# Arduino_Mega_Extended_Breakout_Shield.net
KiCad netlist of a schematic drawn in EAGLE
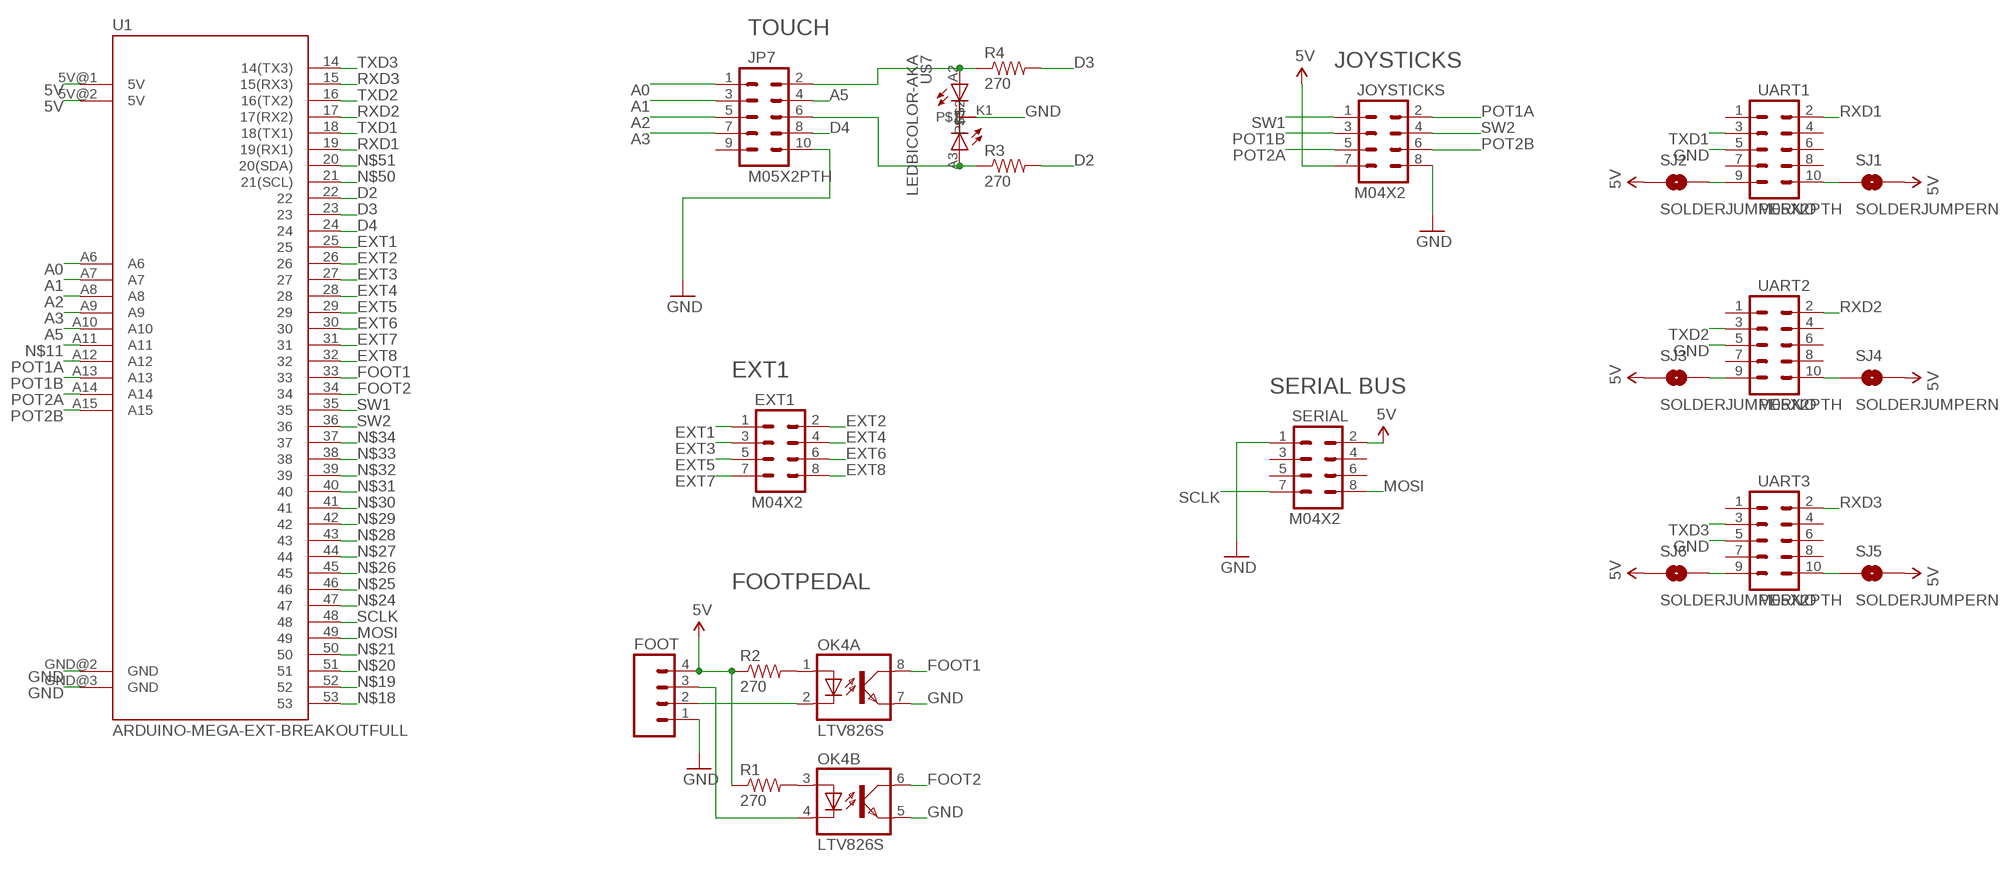
[diagram p0: schematic, sheet 1]

(export (version "E")
  (design (tool "Eeschema 10.0.6"))
  (components
    (comp (ref "EXT1")
      (value "M04X2")
      (footprint "eagle-import:2X4")
      (libsource (lib "eagle-import") (part "M04X2"))
    )
    (comp (ref "FOOT")
      (value "M04LOCK")
      (footprint "eagle-import:1X04_LOCK")
      (libsource (lib "eagle-import") (part "M04LOCK"))
    )
    (comp (ref "JOYSTICKS")
      (value "M04X2")
      (footprint "eagle-import:2X4")
      (libsource (lib "eagle-import") (part "M04X2"))
    )
    (comp (ref "JP7")
      (value "M05X2PTH")
      (footprint "eagle-import:AVR_ICSP")
      (libsource (lib "eagle-import") (part "M05X2PTH"))
    )
    (comp (ref "OK4")
      (value "LTV826S")
      (footprint "eagle-import:DIL8-SMD")
      (libsource (lib "eagle-import") (part "LTV826S"))
    )
    (comp (ref "R1")
      (value "270")
      (footprint "eagle-import:0603-RES")
      (libsource (lib "eagle-import") (part "RESISTOR0603-RES"))
    )
    (comp (ref "R2")
      (value "270")
      (footprint "eagle-import:0603-RES")
      (libsource (lib "eagle-import") (part "RESISTOR0603-RES"))
    )
    (comp (ref "R3")
      (value "270")
      (footprint "eagle-import:0603-RES")
      (libsource (lib "eagle-import") (part "RESISTOR0603-RES"))
    )
    (comp (ref "R4")
      (value "270")
      (footprint "eagle-import:0603-RES")
      (libsource (lib "eagle-import") (part "RESISTOR0603-RES"))
    )
    (comp (ref "SERIAL")
      (value "M04X2")
      (footprint "eagle-import:2X4")
      (libsource (lib "eagle-import") (part "M04X2"))
    )
    (comp (ref "SJ1")
      (value "SOLDERJUMPERNO")
      (footprint "eagle-import:SJ_2S-NO")
      (libsource (lib "eagle-import") (part "SOLDERJUMPERNO"))
    )
    (comp (ref "SJ2")
      (value "SOLDERJUMPERNO")
      (footprint "eagle-import:SJ_2S-NO")
      (libsource (lib "eagle-import") (part "SOLDERJUMPERNO"))
    )
    (comp (ref "SJ3")
      (value "SOLDERJUMPERNO")
      (footprint "eagle-import:SJ_2S-NO")
      (libsource (lib "eagle-import") (part "SOLDERJUMPERNO"))
    )
    (comp (ref "SJ4")
      (value "SOLDERJUMPERNO")
      (footprint "eagle-import:SJ_2S-NO")
      (libsource (lib "eagle-import") (part "SOLDERJUMPERNO"))
    )
    (comp (ref "SJ5")
      (value "SOLDERJUMPERNO")
      (footprint "eagle-import:SJ_2S-NO")
      (libsource (lib "eagle-import") (part "SOLDERJUMPERNO"))
    )
    (comp (ref "SJ6")
      (value "SOLDERJUMPERNO")
      (footprint "eagle-import:SJ_2S-NO")
      (libsource (lib "eagle-import") (part "SOLDERJUMPERNO"))
    )
    (comp (ref "U$7")
      (value "LEDBICOLOR-AKA")
      (footprint "eagle-import:LED5MM-BICOLOR")
      (libsource (lib "eagle-import") (part "LEDBICOLOR-AKA"))
    )
    (comp (ref "U1")
      (value "ARDUINO-MEGA-EXT-BREAKOUTFULL")
      (footprint "eagle-import:ARDUINO_MEGA_EXT_BREAKOUT")
      (libsource (lib "eagle-import") (part "ARDUINO-MEGA-EXT-BREAKOUTFULL"))
    )
    (comp (ref "UART1")
      (value "M05X2PTH")
      (footprint "eagle-import:AVR_ICSP")
      (libsource (lib "eagle-import") (part "M05X2PTH"))
    )
    (comp (ref "UART2")
      (value "M05X2PTH")
      (footprint "eagle-import:AVR_ICSP")
      (libsource (lib "eagle-import") (part "M05X2PTH"))
    )
    (comp (ref "UART3")
      (value "M05X2PTH")
      (footprint "eagle-import:AVR_ICSP")
      (libsource (lib "eagle-import") (part "M05X2PTH"))
    )
  )
  (nets
    (net (code "1") (name "/A0") (class "Default")
      (node (ref "JP7") (pin "1") (pinfunction "1_1") (pintype "passive"))
      (node (ref "U1") (pin "A6") (pinfunction "A6_A6") (pintype "bidirectional"))
    )
    (net (code "2") (name "/A1") (class "Default")
      (node (ref "JP7") (pin "3") (pinfunction "3_3") (pintype "passive"))
      (node (ref "U1") (pin "A7") (pinfunction "A7_A7") (pintype "bidirectional"))
    )
    (net (code "3") (name "/A2") (class "Default")
      (node (ref "JP7") (pin "5") (pinfunction "5_5") (pintype "passive"))
      (node (ref "U1") (pin "A8") (pinfunction "A8_A8") (pintype "bidirectional"))
    )
    (net (code "4") (name "/A3") (class "Default")
      (node (ref "JP7") (pin "7") (pinfunction "7_7") (pintype "passive"))
      (node (ref "U1") (pin "A9") (pinfunction "A9_A9") (pintype "bidirectional"))
    )
    (net (code "5") (name "/A5") (class "Default")
      (node (ref "JP7") (pin "4") (pinfunction "4_4") (pintype "passive"))
      (node (ref "U1") (pin "A10") (pinfunction "A10_A10") (pintype "bidirectional"))
    )
    (net (code "6") (name "/D2") (class "Default")
      (node (ref "R3") (pin "2") (pinfunction "2_2") (pintype "passive"))
      (node (ref "U1") (pin "22") (pinfunction "22_22") (pintype "bidirectional"))
    )
    (net (code "7") (name "/D3") (class "Default")
      (node (ref "R4") (pin "2") (pinfunction "2_2") (pintype "passive"))
      (node (ref "U1") (pin "23") (pinfunction "23_23") (pintype "bidirectional"))
    )
    (net (code "8") (name "/D4") (class "Default")
      (node (ref "JP7") (pin "8") (pinfunction "8_8") (pintype "passive"))
      (node (ref "U1") (pin "24") (pinfunction "24_24") (pintype "bidirectional"))
    )
    (net (code "9") (name "/EXT1") (class "Default")
      (node (ref "EXT1") (pin "1") (pinfunction "1_1") (pintype "passive"))
      (node (ref "U1") (pin "25") (pinfunction "25_25") (pintype "bidirectional"))
    )
    (net (code "10") (name "/EXT2") (class "Default")
      (node (ref "EXT1") (pin "2") (pinfunction "2_2") (pintype "passive"))
      (node (ref "U1") (pin "26") (pinfunction "26_26") (pintype "bidirectional"))
    )
    (net (code "11") (name "/EXT3") (class "Default")
      (node (ref "EXT1") (pin "3") (pinfunction "3_3") (pintype "passive"))
      (node (ref "U1") (pin "27") (pinfunction "27_27") (pintype "bidirectional"))
    )
    (net (code "12") (name "/EXT4") (class "Default")
      (node (ref "EXT1") (pin "4") (pinfunction "4_4") (pintype "passive"))
      (node (ref "U1") (pin "28") (pinfunction "28_28") (pintype "bidirectional"))
    )
    (net (code "13") (name "/EXT5") (class "Default")
      (node (ref "EXT1") (pin "5") (pinfunction "5_5") (pintype "passive"))
      (node (ref "U1") (pin "29") (pinfunction "29_29") (pintype "bidirectional"))
    )
    (net (code "14") (name "/EXT6") (class "Default")
      (node (ref "EXT1") (pin "6") (pinfunction "6_6") (pintype "passive"))
      (node (ref "U1") (pin "30") (pinfunction "30_30") (pintype "bidirectional"))
    )
    (net (code "15") (name "/EXT7") (class "Default")
      (node (ref "EXT1") (pin "7") (pinfunction "7_7") (pintype "passive"))
      (node (ref "U1") (pin "31") (pinfunction "31_31") (pintype "bidirectional"))
    )
    (net (code "16") (name "/EXT8") (class "Default")
      (node (ref "EXT1") (pin "8") (pinfunction "8_8") (pintype "passive"))
      (node (ref "U1") (pin "32") (pinfunction "32_32") (pintype "bidirectional"))
    )
    (net (code "17") (name "/FOOT1") (class "Default")
      (node (ref "OK4") (pin "8") (pinfunction "COL_8") (pintype "passive"))
      (node (ref "U1") (pin "33") (pinfunction "33_33") (pintype "bidirectional"))
    )
    (net (code "18") (name "/FOOT2") (class "Default")
      (node (ref "OK4") (pin "6") (pinfunction "COL_6") (pintype "passive"))
      (node (ref "U1") (pin "34") (pinfunction "34_34") (pintype "bidirectional"))
    )
    (net (code "19") (name "/MOSI") (class "Default")
      (node (ref "SERIAL") (pin "8") (pinfunction "8_8") (pintype "passive"))
      (node (ref "U1") (pin "49") (pinfunction "49_49") (pintype "bidirectional"))
    )
    (net (code "20") (name "/N$11") (class "Default")
      (node (ref "U1") (pin "A11") (pinfunction "A11_A11") (pintype "bidirectional"))
    )
    (net (code "21") (name "/N$18") (class "Default")
      (node (ref "U1") (pin "53") (pinfunction "53_53") (pintype "bidirectional"))
    )
    (net (code "22") (name "/N$19") (class "Default")
      (node (ref "U1") (pin "52") (pinfunction "52_52") (pintype "bidirectional"))
    )
    (net (code "23") (name "/N$20") (class "Default")
      (node (ref "U1") (pin "51") (pinfunction "51_51") (pintype "bidirectional"))
    )
    (net (code "24") (name "/N$21") (class "Default")
      (node (ref "U1") (pin "50") (pinfunction "50_50") (pintype "bidirectional"))
    )
    (net (code "25") (name "/N$24") (class "Default")
      (node (ref "U1") (pin "47") (pinfunction "47_47") (pintype "bidirectional"))
    )
    (net (code "26") (name "/N$25") (class "Default")
      (node (ref "U1") (pin "46") (pinfunction "46_46") (pintype "bidirectional"))
    )
    (net (code "27") (name "/N$26") (class "Default")
      (node (ref "U1") (pin "45") (pinfunction "45_45") (pintype "bidirectional"))
    )
    (net (code "28") (name "/N$27") (class "Default")
      (node (ref "U1") (pin "44") (pinfunction "44_44") (pintype "bidirectional"))
    )
    (net (code "29") (name "/N$28") (class "Default")
      (node (ref "U1") (pin "43") (pinfunction "43_43") (pintype "bidirectional"))
    )
    (net (code "30") (name "/N$29") (class "Default")
      (node (ref "U1") (pin "42") (pinfunction "42_42") (pintype "bidirectional"))
    )
    (net (code "31") (name "/N$30") (class "Default")
      (node (ref "U1") (pin "41") (pinfunction "41_41") (pintype "bidirectional"))
    )
    (net (code "32") (name "/N$31") (class "Default")
      (node (ref "U1") (pin "40") (pinfunction "40_40") (pintype "bidirectional"))
    )
    (net (code "33") (name "/N$32") (class "Default")
      (node (ref "U1") (pin "39") (pinfunction "39_39") (pintype "bidirectional"))
    )
    (net (code "34") (name "/N$33") (class "Default")
      (node (ref "U1") (pin "38") (pinfunction "38_38") (pintype "bidirectional"))
    )
    (net (code "35") (name "/N$34") (class "Default")
      (node (ref "U1") (pin "37") (pinfunction "37_37") (pintype "bidirectional"))
    )
    (net (code "36") (name "/N$50") (class "Default")
      (node (ref "U1") (pin "21") (pinfunction "21(SCL)_21") (pintype "bidirectional"))
    )
    (net (code "37") (name "/N$51") (class "Default")
      (node (ref "U1") (pin "20") (pinfunction "20(SDA)_20") (pintype "bidirectional"))
    )
    (net (code "38") (name "/POT1A") (class "Default")
      (node (ref "JOYSTICKS") (pin "2") (pinfunction "2_2") (pintype "passive"))
      (node (ref "U1") (pin "A12") (pinfunction "A12_A12") (pintype "bidirectional"))
    )
    (net (code "39") (name "/POT1B") (class "Default")
      (node (ref "JOYSTICKS") (pin "3") (pinfunction "3_3") (pintype "passive"))
      (node (ref "U1") (pin "A13") (pinfunction "A13_A13") (pintype "bidirectional"))
    )
    (net (code "40") (name "/POT2A") (class "Default")
      (node (ref "JOYSTICKS") (pin "5") (pinfunction "5_5") (pintype "passive"))
      (node (ref "U1") (pin "A14") (pinfunction "A14_A14") (pintype "bidirectional"))
    )
    (net (code "41") (name "/POT2B") (class "Default")
      (node (ref "JOYSTICKS") (pin "6") (pinfunction "6_6") (pintype "passive"))
      (node (ref "U1") (pin "A15") (pinfunction "A15_A15") (pintype "bidirectional"))
    )
    (net (code "42") (name "/RXD1") (class "Default")
      (node (ref "U1") (pin "19") (pinfunction "19(RX1)_19") (pintype "bidirectional"))
      (node (ref "UART1") (pin "2") (pinfunction "2_2") (pintype "passive"))
    )
    (net (code "43") (name "/RXD2") (class "Default")
      (node (ref "U1") (pin "17") (pinfunction "17(RX2)_17") (pintype "bidirectional"))
      (node (ref "UART2") (pin "2") (pinfunction "2_2") (pintype "passive"))
    )
    (net (code "44") (name "/RXD3") (class "Default")
      (node (ref "U1") (pin "15") (pinfunction "15(RX3)_15") (pintype "bidirectional"))
      (node (ref "UART3") (pin "2") (pinfunction "2_2") (pintype "passive"))
    )
    (net (code "45") (name "/SCLK") (class "Default")
      (node (ref "SERIAL") (pin "7") (pinfunction "7_7") (pintype "passive"))
      (node (ref "U1") (pin "48") (pinfunction "48_48") (pintype "bidirectional"))
    )
    (net (code "46") (name "/SW1") (class "Default")
      (node (ref "JOYSTICKS") (pin "1") (pinfunction "1_1") (pintype "passive"))
      (node (ref "U1") (pin "35") (pinfunction "35_35") (pintype "bidirectional"))
    )
    (net (code "47") (name "/SW2") (class "Default")
      (node (ref "JOYSTICKS") (pin "4") (pinfunction "4_4") (pintype "passive"))
      (node (ref "U1") (pin "36") (pinfunction "36_36") (pintype "bidirectional"))
    )
    (net (code "48") (name "/TXD1") (class "Default")
      (node (ref "U1") (pin "18") (pinfunction "18(TX1)_18") (pintype "bidirectional"))
      (node (ref "UART1") (pin "3") (pinfunction "3_3") (pintype "passive"))
    )
    (net (code "49") (name "/TXD2") (class "Default")
      (node (ref "U1") (pin "16") (pinfunction "16(TX2)_16") (pintype "bidirectional"))
      (node (ref "UART2") (pin "3") (pinfunction "3_3") (pintype "passive"))
    )
    (net (code "50") (name "/TXD3") (class "Default")
      (node (ref "U1") (pin "14") (pinfunction "14(TX3)_14") (pintype "bidirectional"))
      (node (ref "UART3") (pin "3") (pinfunction "3_3") (pintype "passive"))
    )
    (net (code "51") (name "5V") (class "Default")
      (node (ref "FOOT") (pin "4") (pinfunction "4_4") (pintype "passive"))
      (node (ref "JOYSTICKS") (pin "7") (pinfunction "7_7") (pintype "passive"))
      (node (ref "R1") (pin "1") (pinfunction "1_1") (pintype "passive"))
      (node (ref "R2") (pin "1") (pinfunction "1_1") (pintype "passive"))
      (node (ref "SERIAL") (pin "2") (pinfunction "2_2") (pintype "passive"))
      (node (ref "SJ1") (pin "2") (pinfunction "2_2") (pintype "passive"))
      (node (ref "SJ2") (pin "1") (pinfunction "1_1") (pintype "passive"))
      (node (ref "SJ3") (pin "1") (pinfunction "1_1") (pintype "passive"))
      (node (ref "SJ4") (pin "2") (pinfunction "2_2") (pintype "passive"))
      (node (ref "SJ5") (pin "2") (pinfunction "2_2") (pintype "passive"))
      (node (ref "SJ6") (pin "1") (pinfunction "1_1") (pintype "passive"))
      (node (ref "U1") (pin "5V@1") (pinfunction "5V_5V@1") (pintype "bidirectional"))
      (node (ref "U1") (pin "5V@2") (pinfunction "5V_5V@2") (pintype "bidirectional"))
    )
    (net (code "52") (name "GND") (class "Default")
      (node (ref "FOOT") (pin "1") (pinfunction "1_1") (pintype "passive"))
      (node (ref "JOYSTICKS") (pin "8") (pinfunction "8_8") (pintype "passive"))
      (node (ref "JP7") (pin "10") (pinfunction "10_10") (pintype "passive"))
      (node (ref "OK4") (pin "5") (pinfunction "EMIT_5") (pintype "passive"))
      (node (ref "OK4") (pin "7") (pinfunction "EMIT_7") (pintype "passive"))
      (node (ref "SERIAL") (pin "1") (pinfunction "1_1") (pintype "passive"))
      (node (ref "U$7") (pin "K1") (pinfunction "P$1_K1") (pintype "bidirectional"))
      (node (ref "U1") (pin "GND@2") (pinfunction "GND_GND@2") (pintype "bidirectional"))
      (node (ref "U1") (pin "GND@3") (pinfunction "GND_GND@3") (pintype "bidirectional"))
      (node (ref "UART1") (pin "5") (pinfunction "5_5") (pintype "passive"))
      (node (ref "UART2") (pin "5") (pinfunction "5_5") (pintype "passive"))
      (node (ref "UART3") (pin "5") (pinfunction "5_5") (pintype "passive"))
    )
    (net (code "53") (name "Net-(OK4A-A)") (class "Default")
      (node (ref "OK4") (pin "1") (pinfunction "A_1") (pintype "passive"))
      (node (ref "R2") (pin "2") (pinfunction "2_2") (pintype "passive"))
    )
    (net (code "54") (name "Net-(OK4A-C)") (class "Default")
      (node (ref "FOOT") (pin "2") (pinfunction "2_2") (pintype "passive"))
      (node (ref "OK4") (pin "2") (pinfunction "C_2") (pintype "passive"))
    )
    (net (code "55") (name "Net-(OK4B-A)") (class "Default")
      (node (ref "OK4") (pin "3") (pinfunction "A_3") (pintype "passive"))
      (node (ref "R1") (pin "2") (pinfunction "2_2") (pintype "passive"))
    )
    (net (code "56") (name "Net-(OK4B-C)") (class "Default")
      (node (ref "FOOT") (pin "3") (pinfunction "3_3") (pintype "passive"))
      (node (ref "OK4") (pin "4") (pinfunction "C_4") (pintype "passive"))
    )
    (net (code "57") (name "Net-(SJ1-Pad1)") (class "Default")
      (node (ref "SJ1") (pin "1") (pinfunction "1_1") (pintype "passive"))
      (node (ref "UART1") (pin "10") (pinfunction "10_10") (pintype "passive"))
    )
    (net (code "58") (name "Net-(SJ2-Pad2)") (class "Default")
      (node (ref "SJ2") (pin "2") (pinfunction "2_2") (pintype "passive"))
      (node (ref "UART1") (pin "9") (pinfunction "9_9") (pintype "passive"))
    )
    (net (code "59") (name "Net-(SJ3-Pad2)") (class "Default")
      (node (ref "SJ3") (pin "2") (pinfunction "2_2") (pintype "passive"))
      (node (ref "UART2") (pin "9") (pinfunction "9_9") (pintype "passive"))
    )
    (net (code "60") (name "Net-(SJ4-Pad1)") (class "Default")
      (node (ref "SJ4") (pin "1") (pinfunction "1_1") (pintype "passive"))
      (node (ref "UART2") (pin "10") (pinfunction "10_10") (pintype "passive"))
    )
    (net (code "61") (name "Net-(SJ5-Pad1)") (class "Default")
      (node (ref "SJ5") (pin "1") (pinfunction "1_1") (pintype "passive"))
      (node (ref "UART3") (pin "10") (pinfunction "10_10") (pintype "passive"))
    )
    (net (code "62") (name "Net-(SJ6-Pad2)") (class "Default")
      (node (ref "SJ6") (pin "2") (pinfunction "2_2") (pintype "passive"))
      (node (ref "UART3") (pin "9") (pinfunction "9_9") (pintype "passive"))
    )
    (net (code "63") (name "Net-(U$7-P$2)") (class "Default")
      (node (ref "JP7") (pin "2") (pinfunction "2_2") (pintype "passive"))
      (node (ref "R4") (pin "1") (pinfunction "1_1") (pintype "passive"))
      (node (ref "U$7") (pin "A2") (pinfunction "P$2_A2") (pintype "bidirectional"))
    )
    (net (code "64") (name "Net-(U$7-P$3)") (class "Default")
      (node (ref "JP7") (pin "6") (pinfunction "6_6") (pintype "passive"))
      (node (ref "R3") (pin "1") (pinfunction "1_1") (pintype "passive"))
      (node (ref "U$7") (pin "A3") (pinfunction "P$3_A3") (pintype "bidirectional"))
    )
    (net (code "65") (name "unconnected-(JP7-Pad9)") (class "Default")
      (node (ref "JP7") (pin "9") (pinfunction "9_9") (pintype "passive"))
    )
    (net (code "66") (name "unconnected-(SERIAL-Pad3)") (class "Default")
      (node (ref "SERIAL") (pin "3") (pinfunction "3_3") (pintype "passive"))
    )
    (net (code "67") (name "unconnected-(SERIAL-Pad4)") (class "Default")
      (node (ref "SERIAL") (pin "4") (pinfunction "4_4") (pintype "passive"))
    )
    (net (code "68") (name "unconnected-(SERIAL-Pad5)") (class "Default")
      (node (ref "SERIAL") (pin "5") (pinfunction "5_5") (pintype "passive"))
    )
    (net (code "69") (name "unconnected-(SERIAL-Pad6)") (class "Default")
      (node (ref "SERIAL") (pin "6") (pinfunction "6_6") (pintype "passive"))
    )
    (net (code "70") (name "unconnected-(UART1-Pad1)") (class "Default")
      (node (ref "UART1") (pin "1") (pinfunction "1_1") (pintype "passive"))
    )
    (net (code "71") (name "unconnected-(UART1-Pad4)") (class "Default")
      (node (ref "UART1") (pin "4") (pinfunction "4_4") (pintype "passive"))
    )
    (net (code "72") (name "unconnected-(UART1-Pad6)") (class "Default")
      (node (ref "UART1") (pin "6") (pinfunction "6_6") (pintype "passive"))
    )
    (net (code "73") (name "unconnected-(UART1-Pad7)") (class "Default")
      (node (ref "UART1") (pin "7") (pinfunction "7_7") (pintype "passive"))
    )
    (net (code "74") (name "unconnected-(UART1-Pad8)") (class "Default")
      (node (ref "UART1") (pin "8") (pinfunction "8_8") (pintype "passive"))
    )
    (net (code "75") (name "unconnected-(UART2-Pad1)") (class "Default")
      (node (ref "UART2") (pin "1") (pinfunction "1_1") (pintype "passive"))
    )
    (net (code "76") (name "unconnected-(UART2-Pad4)") (class "Default")
      (node (ref "UART2") (pin "4") (pinfunction "4_4") (pintype "passive"))
    )
    (net (code "77") (name "unconnected-(UART2-Pad6)") (class "Default")
      (node (ref "UART2") (pin "6") (pinfunction "6_6") (pintype "passive"))
    )
    (net (code "78") (name "unconnected-(UART2-Pad7)") (class "Default")
      (node (ref "UART2") (pin "7") (pinfunction "7_7") (pintype "passive"))
    )
    (net (code "79") (name "unconnected-(UART2-Pad8)") (class "Default")
      (node (ref "UART2") (pin "8") (pinfunction "8_8") (pintype "passive"))
    )
    (net (code "80") (name "unconnected-(UART3-Pad1)") (class "Default")
      (node (ref "UART3") (pin "1") (pinfunction "1_1") (pintype "passive"))
    )
    (net (code "81") (name "unconnected-(UART3-Pad4)") (class "Default")
      (node (ref "UART3") (pin "4") (pinfunction "4_4") (pintype "passive"))
    )
    (net (code "82") (name "unconnected-(UART3-Pad6)") (class "Default")
      (node (ref "UART3") (pin "6") (pinfunction "6_6") (pintype "passive"))
    )
    (net (code "83") (name "unconnected-(UART3-Pad7)") (class "Default")
      (node (ref "UART3") (pin "7") (pinfunction "7_7") (pintype "passive"))
    )
    (net (code "84") (name "unconnected-(UART3-Pad8)") (class "Default")
      (node (ref "UART3") (pin "8") (pinfunction "8_8") (pintype "passive"))
    )
  )
)
